# dexv1.net
KiCad netlist of a schematic drawn in EAGLE
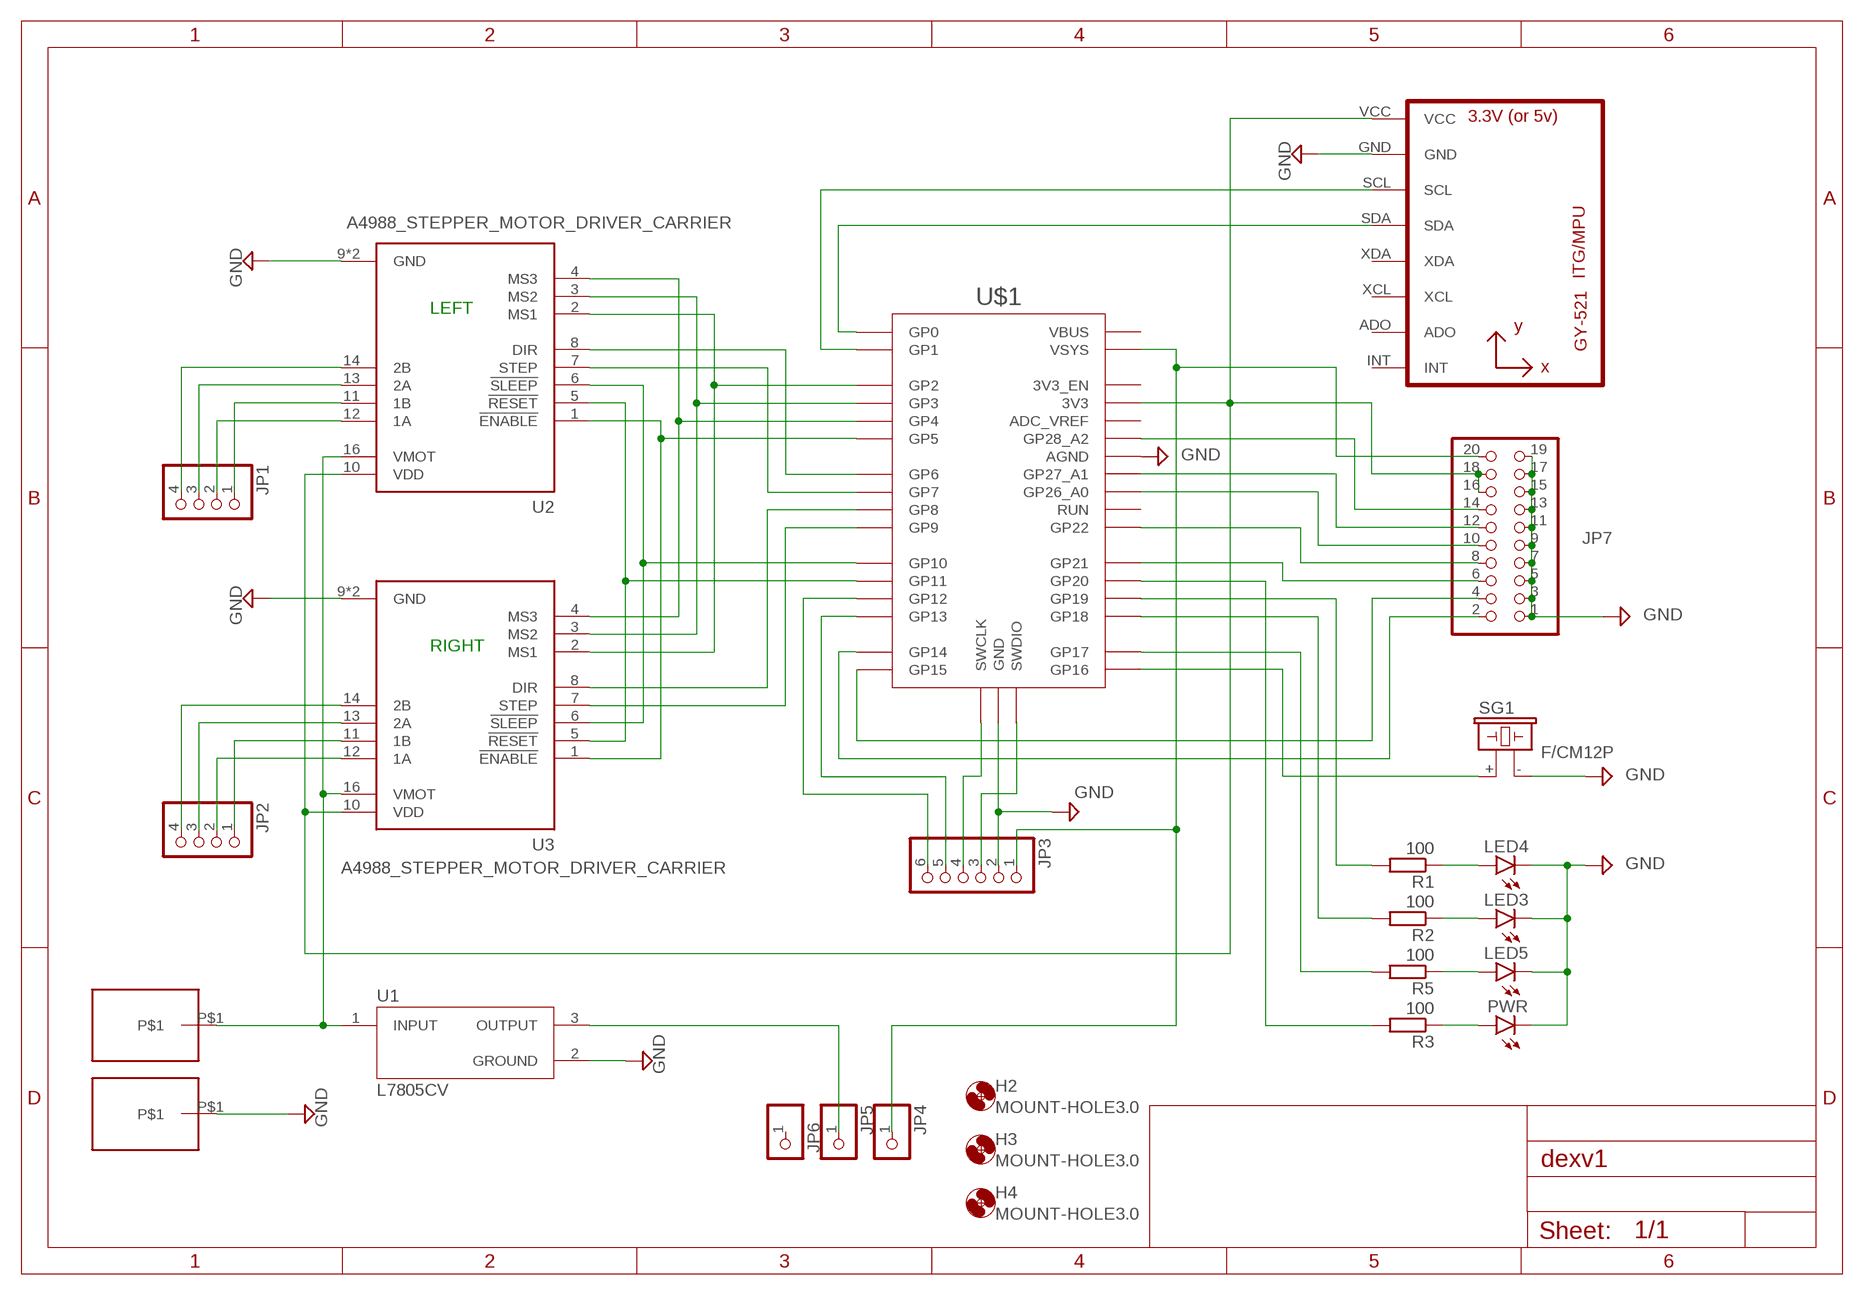
[diagram p0: schematic, sheet 1]

(export (version "E")
  (design (tool "Eeschema 10.0.6"))
  (components
    (comp (ref "H2")
      (value "MOUNT-HOLE3.0")
      (footprint "eagle-import:3,0")
      (libsource (lib "eagle-import") (part "MOUNT-HOLE3.0"))
    )
    (comp (ref "H3")
      (value "MOUNT-HOLE3.0")
      (footprint "eagle-import:3,0")
      (libsource (lib "eagle-import") (part "MOUNT-HOLE3.0"))
    )
    (comp (ref "H4")
      (value "MOUNT-HOLE3.0")
      (footprint "eagle-import:3,0")
      (libsource (lib "eagle-import") (part "MOUNT-HOLE3.0"))
    )
    (comp (ref "JP1")
      (value "PINHD-1X4")
      (footprint "eagle-import:1X04")
      (libsource (lib "eagle-import") (part "PINHD-1X4"))
    )
    (comp (ref "JP2")
      (value "PINHD-1X4")
      (footprint "eagle-import:1X04")
      (libsource (lib "eagle-import") (part "PINHD-1X4"))
    )
    (comp (ref "JP3")
      (value "PINHD-1X6")
      (footprint "eagle-import:1X06")
      (libsource (lib "eagle-import") (part "PINHD-1X6"))
    )
    (comp (ref "JP4")
      (value "PINHD-1X1")
      (footprint "eagle-import:1X01")
      (libsource (lib "eagle-import") (part "PINHD-1X1"))
    )
    (comp (ref "JP5")
      (value "PINHD-1X1")
      (footprint "eagle-import:1X01")
      (libsource (lib "eagle-import") (part "PINHD-1X1"))
    )
    (comp (ref "JP6")
      (value "PINHD-1X1")
      (footprint "eagle-import:1X01")
      (libsource (lib "eagle-import") (part "PINHD-1X1"))
    )
    (comp (ref "JP7")
      (value "PINHD-2X10")
      (footprint "eagle-import:2X10")
      (libsource (lib "eagle-import") (part "PINHD-2X10"))
    )
    (comp (ref "LED3")
      (value "LED5MM")
      (footprint "eagle-import:LED5MM")
      (libsource (lib "eagle-import") (part "LED5MM"))
    )
    (comp (ref "LED4")
      (value "LED5MM")
      (footprint "eagle-import:LED5MM")
      (libsource (lib "eagle-import") (part "LED5MM"))
    )
    (comp (ref "LED5")
      (value "LED5MM")
      (footprint "eagle-import:LED5MM")
      (libsource (lib "eagle-import") (part "LED5MM"))
    )
    (comp (ref "PWR")
      (value "LED5MM")
      (footprint "eagle-import:LED5MM")
      (libsource (lib "eagle-import") (part "LED5MM"))
    )
    (comp (ref "R1")
      (value "100")
      (footprint "eagle-import:0204_7")
      (libsource (lib "eagle-import") (part "R-EU_0204/7"))
    )
    (comp (ref "R2")
      (value "100")
      (footprint "eagle-import:0204_7")
      (libsource (lib "eagle-import") (part "R-EU_0204/7"))
    )
    (comp (ref "R3")
      (value "100")
      (footprint "eagle-import:0204_7")
      (libsource (lib "eagle-import") (part "R-EU_0204/7"))
    )
    (comp (ref "R5")
      (value "100")
      (footprint "eagle-import:0204_7")
      (libsource (lib "eagle-import") (part "R-EU_0204/7"))
    )
    (comp (ref "SG1")
      (value "F/CM12P")
      (footprint "eagle-import:F_CM12P")
      (libsource (lib "eagle-import") (part "F/CM12P"))
    )
    (comp (ref "U$1")
      (value "RPI_PICO-TH")
      (footprint "eagle-import:RPI_PICO_TH")
      (libsource (lib "eagle-import") (part "RPI_PICO-TH"))
    )
    (comp (ref "U$2")
      (value "SMD5X10")
      (footprint "eagle-import:SMD5X10")
      (libsource (lib "eagle-import") (part "SMD5X10"))
    )
    (comp (ref "U$3")
      (value "SMD5X10")
      (footprint "eagle-import:SMD5X10")
      (libsource (lib "eagle-import") (part "SMD5X10"))
    )
    (comp (ref "U1")
      (value "L7805CV")
      (footprint "eagle-import:TO255P1040X460X1968-3")
      (fields (field (name "MF") "STMicroelectronics") (field (name "MP") "L7805C-V"))
      (libsource (lib "eagle-import") (part "L7805CV"))
    )
    (comp (ref "U2")
      (value "A4988_STEPPER_MOTOR_DRIVER_CARRIER")
      (footprint "eagle-import:MODULE_A4988_STEPPER_MOTOR_DRIVER_CARRIER")
      (fields (field (name "MF") "Pololu") (field (name "MP") "A4988 STEPPER MOTOR DRIVER CARRIER"))
      (libsource (lib "eagle-import") (part "A4988_STEPPER_MOTOR_DRIVER_CARRIER"))
    )
    (comp (ref "U3")
      (value "A4988_STEPPER_MOTOR_DRIVER_CARRIER")
      (footprint "eagle-import:MODULE_A4988_STEPPER_MOTOR_DRIVER_CARRIER")
      (fields (field (name "MF") "Pololu") (field (name "MP") "A4988 STEPPER MOTOR DRIVER CARRIER"))
      (libsource (lib "eagle-import") (part "A4988_STEPPER_MOTOR_DRIVER_CARRIER"))
    )
    (comp (ref "U4")
      (value "GY-521MPU6050")
      (footprint "eagle-import:GY-521")
      (fields (field (name "MF") "GODREAM FORDREAM CO., LIMITED") (field (name "MP") "GY-521"))
      (libsource (lib "eagle-import") (part "GY-521MPU6050"))
    )
  )
  (nets
    (net (code "1") (name "GND") (class "Default")
      (node (ref "JP3") (pin "2") (pinfunction "2_2") (pintype "passive"))
      (node (ref "JP7") (pin "1") (pinfunction "1_1") (pintype "passive"))
      (node (ref "JP7") (pin "11") (pinfunction "11_11") (pintype "passive"))
      (node (ref "JP7") (pin "13") (pinfunction "13_13") (pintype "passive"))
      (node (ref "JP7") (pin "15") (pinfunction "15_15") (pintype "passive"))
      (node (ref "JP7") (pin "17") (pinfunction "17_17") (pintype "passive"))
      (node (ref "JP7") (pin "19") (pinfunction "19_19") (pintype "passive"))
      (node (ref "JP7") (pin "3") (pinfunction "3_3") (pintype "passive"))
      (node (ref "JP7") (pin "5") (pinfunction "5_5") (pintype "passive"))
      (node (ref "JP7") (pin "7") (pinfunction "7_7") (pintype "passive"))
      (node (ref "JP7") (pin "9") (pinfunction "9_9") (pintype "passive"))
      (node (ref "LED3") (pin "K") (pinfunction "C_K") (pintype "passive"))
      (node (ref "LED4") (pin "K") (pinfunction "C_K") (pintype "passive"))
      (node (ref "LED5") (pin "K") (pinfunction "C_K") (pintype "passive"))
      (node (ref "PWR") (pin "K") (pinfunction "C_K") (pintype "passive"))
      (node (ref "SG1") (pin "-") (pinfunction "2_-") (pintype "passive"))
      (node (ref "U$1") (pin "AGND") (pinfunction "AGND_AGND") (pintype "bidirectional"))
      (node (ref "U$1") (pin "GND@1") (pinfunction "GND_GND@1") (pintype "bidirectional"))
      (node (ref "U$1") (pin "GND@2") (pinfunction "GND_GND@2") (pintype "bidirectional"))
      (node (ref "U$1") (pin "GND@3") (pinfunction "GND_GND@3") (pintype "bidirectional"))
      (node (ref "U$1") (pin "GND@4") (pinfunction "GND_GND@4") (pintype "bidirectional"))
      (node (ref "U$1") (pin "GND@5") (pinfunction "GND_GND@5") (pintype "bidirectional"))
      (node (ref "U$1") (pin "GND@6") (pinfunction "GND_GND@6") (pintype "bidirectional"))
      (node (ref "U$1") (pin "GND@7") (pinfunction "GND_GND@7") (pintype "bidirectional"))
      (node (ref "U$1") (pin "GND@8") (pinfunction "GND_GND@8") (pintype "bidirectional"))
      (node (ref "U$1") (pin "P$2") (pinfunction "GND_P$2") (pintype "bidirectional"))
      (node (ref "U$3") (pin "P$1") (pinfunction "P$1_P$1") (pintype "bidirectional"))
      (node (ref "U1") (pin "2") (pinfunction "GROUND_2") (pintype "power_in"))
      (node (ref "U2") (pin "15") (pinfunction "GND_15") (pintype "power_in"))
      (node (ref "U2") (pin "9") (pinfunction "GND_9") (pintype "power_in"))
      (node (ref "U3") (pin "15") (pinfunction "GND_15") (pintype "power_in"))
      (node (ref "U3") (pin "9") (pinfunction "GND_9") (pintype "power_in"))
      (node (ref "U4") (pin "GND") (pinfunction "GND_GND") (pintype "bidirectional"))
    )
    (net (code "2") (name "Net-(JP3-Pad1)") (class "Default")
      (node (ref "JP3") (pin "1") (pinfunction "1_1") (pintype "passive"))
      (node (ref "JP4") (pin "1") (pinfunction "1_1") (pintype "passive"))
      (node (ref "JP7") (pin "20") (pinfunction "20_20") (pintype "passive"))
      (node (ref "U$1") (pin "VSYS") (pinfunction "VSYS_VSYS") (pintype "bidirectional"))
    )
    (net (code "3") (name "Net-(JP3-Pad3)") (class "Default")
      (node (ref "JP3") (pin "3") (pinfunction "3_3") (pintype "passive"))
      (node (ref "U$1") (pin "P$3") (pinfunction "SWDIO_P$3") (pintype "bidirectional"))
      (node (ref "U$1") (pin "SWDIO") (pinfunction "SWDIO_SWDIO") (pintype "bidirectional"))
    )
    (net (code "4") (name "Net-(JP3-Pad4)") (class "Default")
      (node (ref "JP3") (pin "4") (pinfunction "4_4") (pintype "passive"))
      (node (ref "U$1") (pin "P$1") (pinfunction "SWCLK_P$1") (pintype "bidirectional"))
      (node (ref "U$1") (pin "SWCLK") (pinfunction "SWCLK_SWCLK") (pintype "bidirectional"))
    )
    (net (code "5") (name "Net-(JP3-Pad5)") (class "Default")
      (node (ref "JP3") (pin "5") (pinfunction "5_5") (pintype "passive"))
      (node (ref "U$1") (pin "GP13") (pinfunction "GP13_GP13") (pintype "bidirectional"))
    )
    (net (code "6") (name "Net-(JP3-Pad6)") (class "Default")
      (node (ref "JP3") (pin "6") (pinfunction "6_6") (pintype "passive"))
      (node (ref "U$1") (pin "GP12") (pinfunction "GP12_GP12") (pintype "bidirectional"))
    )
    (net (code "7") (name "Net-(JP7-Pad2)") (class "Default")
      (node (ref "JP7") (pin "2") (pinfunction "2_2") (pintype "passive"))
      (node (ref "U$1") (pin "GP14") (pinfunction "GP14_GP14") (pintype "bidirectional"))
    )
    (net (code "8") (name "Net-(JP7-Pad4)") (class "Default")
      (node (ref "JP7") (pin "4") (pinfunction "4_4") (pintype "passive"))
      (node (ref "U$1") (pin "GP15") (pinfunction "GP15_GP15") (pintype "bidirectional"))
    )
    (net (code "9") (name "Net-(JP7-Pad6)") (class "Default")
      (node (ref "JP7") (pin "6") (pinfunction "6_6") (pintype "passive"))
      (node (ref "U$1") (pin "GP21") (pinfunction "GP21_GP21") (pintype "bidirectional"))
    )
    (net (code "10") (name "Net-(JP7-Pad8)") (class "Default")
      (node (ref "JP7") (pin "8") (pinfunction "8_8") (pintype "passive"))
      (node (ref "U$1") (pin "GP22") (pinfunction "GP22_GP22") (pintype "bidirectional"))
    )
    (net (code "11") (name "Net-(JP7-Pad10)") (class "Default")
      (node (ref "JP7") (pin "10") (pinfunction "10_10") (pintype "passive"))
      (node (ref "U$1") (pin "GP26_A0") (pinfunction "GP26_A0_GP26_A0") (pintype "bidirectional"))
    )
    (net (code "12") (name "Net-(JP7-Pad12)") (class "Default")
      (node (ref "JP7") (pin "12") (pinfunction "12_12") (pintype "passive"))
      (node (ref "U$1") (pin "GP27_A1") (pinfunction "GP27_A1_GP27_A1") (pintype "bidirectional"))
    )
    (net (code "13") (name "Net-(JP7-Pad14)") (class "Default")
      (node (ref "JP7") (pin "14") (pinfunction "14_14") (pintype "passive"))
      (node (ref "U$1") (pin "GP28_A2") (pinfunction "GP28_A2_GP28_A2") (pintype "bidirectional"))
    )
    (net (code "14") (name "Net-(LED3-PadA)") (class "Default")
      (node (ref "LED3") (pin "A") (pinfunction "A_A") (pintype "passive"))
      (node (ref "R2") (pin "1") (pinfunction "1_1") (pintype "passive"))
    )
    (net (code "15") (name "Net-(LED4-PadA)") (class "Default")
      (node (ref "LED4") (pin "A") (pinfunction "A_A") (pintype "passive"))
      (node (ref "R1") (pin "1") (pinfunction "1_1") (pintype "passive"))
    )
    (net (code "16") (name "Net-(LED5-PadA)") (class "Default")
      (node (ref "LED5") (pin "A") (pinfunction "A_A") (pintype "passive"))
      (node (ref "R5") (pin "1") (pinfunction "1_1") (pintype "passive"))
    )
    (net (code "17") (name "Net-(PWR-PadA)") (class "Default")
      (node (ref "PWR") (pin "A") (pinfunction "A_A") (pintype "passive"))
      (node (ref "R3") (pin "1") (pinfunction "1_1") (pintype "passive"))
    )
    (net (code "18") (name "Net-(R1-Pad2)") (class "Default")
      (node (ref "R1") (pin "2") (pinfunction "2_2") (pintype "passive"))
      (node (ref "U$1") (pin "GP19") (pinfunction "GP19_GP19") (pintype "bidirectional"))
    )
    (net (code "19") (name "Net-(R2-Pad2)") (class "Default")
      (node (ref "R2") (pin "2") (pinfunction "2_2") (pintype "passive"))
      (node (ref "U$1") (pin "GP18") (pinfunction "GP18_GP18") (pintype "bidirectional"))
    )
    (net (code "20") (name "Net-(R3-Pad2)") (class "Default")
      (node (ref "R3") (pin "2") (pinfunction "2_2") (pintype "passive"))
      (node (ref "U$1") (pin "GP20") (pinfunction "GP20_GP20") (pintype "bidirectional"))
    )
    (net (code "21") (name "Net-(R5-Pad2)") (class "Default")
      (node (ref "R5") (pin "2") (pinfunction "2_2") (pintype "passive"))
      (node (ref "U$1") (pin "GP17") (pinfunction "GP17_GP17") (pintype "bidirectional"))
    )
    (net (code "22") (name "Net-(SG1-1)") (class "Default")
      (node (ref "SG1") (pin "+") (pinfunction "1_+") (pintype "passive"))
      (node (ref "U$1") (pin "GP16") (pinfunction "GP16_GP16") (pintype "bidirectional"))
    )
    (net (code "23") (name "Net-(U$1-PadGP0)") (class "Default")
      (node (ref "U$1") (pin "GP0") (pinfunction "GP0_GP0") (pintype "bidirectional"))
      (node (ref "U4") (pin "SDA") (pinfunction "SDA_SDA") (pintype "bidirectional"))
    )
    (net (code "24") (name "Net-(U$1-PadGP1)") (class "Default")
      (node (ref "U$1") (pin "GP1") (pinfunction "GP1_GP1") (pintype "bidirectional"))
      (node (ref "U4") (pin "SCL") (pinfunction "SCL_SCL") (pintype "bidirectional"))
    )
    (net (code "25") (name "Net-(U1-INPUT)") (class "Default")
      (node (ref "U$2") (pin "P$1") (pinfunction "P$1_P$1") (pintype "bidirectional"))
      (node (ref "U1") (pin "1") (pinfunction "INPUT_1") (pintype "input"))
      (node (ref "U2") (pin "16") (pinfunction "VMOT_16") (pintype "power_in"))
      (node (ref "U3") (pin "16") (pinfunction "VMOT_16") (pintype "power_in"))
    )
    (net (code "26") (name "Net-(U1-OUTPUT)") (class "Default")
      (node (ref "JP5") (pin "1") (pinfunction "1_1") (pintype "passive"))
      (node (ref "U1") (pin "3") (pinfunction "OUTPUT_3") (pintype "output"))
    )
    (net (code "27") (name "Net-(U2-1A)") (class "Default")
      (node (ref "JP1") (pin "2") (pinfunction "2_2") (pintype "passive"))
      (node (ref "U2") (pin "12") (pinfunction "1A_12") (pintype "output"))
    )
    (net (code "28") (name "Net-(U2-1B)") (class "Default")
      (node (ref "JP1") (pin "1") (pinfunction "1_1") (pintype "passive"))
      (node (ref "U2") (pin "11") (pinfunction "1B_11") (pintype "output"))
    )
    (net (code "29") (name "Net-(U2-2A)") (class "Default")
      (node (ref "JP1") (pin "3") (pinfunction "3_3") (pintype "passive"))
      (node (ref "U2") (pin "13") (pinfunction "2A_13") (pintype "output"))
    )
    (net (code "30") (name "Net-(U2-2B)") (class "Default")
      (node (ref "JP1") (pin "4") (pinfunction "4_4") (pintype "passive"))
      (node (ref "U2") (pin "14") (pinfunction "2B_14") (pintype "output"))
    )
    (net (code "31") (name "Net-(U2-DIR)") (class "Default")
      (node (ref "U$1") (pin "GP6") (pinfunction "GP6_GP6") (pintype "bidirectional"))
      (node (ref "U2") (pin "8") (pinfunction "DIR_8") (pintype "input"))
    )
    (net (code "32") (name "Net-(U2-MS1)") (class "Default")
      (node (ref "U$1") (pin "GP2") (pinfunction "GP2_GP2") (pintype "bidirectional"))
      (node (ref "U2") (pin "2") (pinfunction "MS1_2") (pintype "input"))
      (node (ref "U3") (pin "2") (pinfunction "MS1_2") (pintype "input"))
    )
    (net (code "33") (name "Net-(U2-MS2)") (class "Default")
      (node (ref "U$1") (pin "GP3") (pinfunction "GP3_GP3") (pintype "bidirectional"))
      (node (ref "U2") (pin "3") (pinfunction "MS2_3") (pintype "input"))
      (node (ref "U3") (pin "3") (pinfunction "MS2_3") (pintype "input"))
    )
    (net (code "34") (name "Net-(U2-MS3)") (class "Default")
      (node (ref "U$1") (pin "GP4") (pinfunction "GP4_GP4") (pintype "bidirectional"))
      (node (ref "U2") (pin "4") (pinfunction "MS3_4") (pintype "input"))
      (node (ref "U3") (pin "4") (pinfunction "MS3_4") (pintype "input"))
    )
    (net (code "35") (name "Net-(U2-STEP)") (class "Default")
      (node (ref "U$1") (pin "GP7") (pinfunction "GP7_GP7") (pintype "bidirectional"))
      (node (ref "U2") (pin "7") (pinfunction "STEP_7") (pintype "input"))
    )
    (net (code "36") (name "Net-(U2-VDD)") (class "Default")
      (node (ref "JP7") (pin "16") (pinfunction "16_16") (pintype "passive"))
      (node (ref "JP7") (pin "18") (pinfunction "18_18") (pintype "passive"))
      (node (ref "U$1") (pin "3V3") (pinfunction "3V3_3V3") (pintype "bidirectional"))
      (node (ref "U2") (pin "10") (pinfunction "VDD_10") (pintype "power_in"))
      (node (ref "U3") (pin "10") (pinfunction "VDD_10") (pintype "power_in"))
      (node (ref "U4") (pin "VCC") (pinfunction "VCC_VCC") (pintype "bidirectional"))
    )
    (net (code "37") (name "Net-(U2-~{ENABLE})") (class "Default")
      (node (ref "U$1") (pin "GP5") (pinfunction "GP5_GP5") (pintype "bidirectional"))
      (node (ref "U2") (pin "1") (pinfunction "~{ENABLE}_1") (pintype "input"))
      (node (ref "U3") (pin "1") (pinfunction "~{ENABLE}_1") (pintype "input"))
    )
    (net (code "38") (name "Net-(U2-~{RESET})") (class "Default")
      (node (ref "U$1") (pin "GP11") (pinfunction "GP11_GP11") (pintype "bidirectional"))
      (node (ref "U2") (pin "5") (pinfunction "~{RESET}_5") (pintype "input"))
      (node (ref "U3") (pin "5") (pinfunction "~{RESET}_5") (pintype "input"))
    )
    (net (code "39") (name "Net-(U2-~{SLEEP})") (class "Default")
      (node (ref "U$1") (pin "GP10") (pinfunction "GP10_GP10") (pintype "bidirectional"))
      (node (ref "U2") (pin "6") (pinfunction "~{SLEEP}_6") (pintype "input"))
      (node (ref "U3") (pin "6") (pinfunction "~{SLEEP}_6") (pintype "input"))
    )
    (net (code "40") (name "Net-(U3-1A)") (class "Default")
      (node (ref "JP2") (pin "2") (pinfunction "2_2") (pintype "passive"))
      (node (ref "U3") (pin "12") (pinfunction "1A_12") (pintype "output"))
    )
    (net (code "41") (name "Net-(U3-1B)") (class "Default")
      (node (ref "JP2") (pin "1") (pinfunction "1_1") (pintype "passive"))
      (node (ref "U3") (pin "11") (pinfunction "1B_11") (pintype "output"))
    )
    (net (code "42") (name "Net-(U3-2A)") (class "Default")
      (node (ref "JP2") (pin "3") (pinfunction "3_3") (pintype "passive"))
      (node (ref "U3") (pin "13") (pinfunction "2A_13") (pintype "output"))
    )
    (net (code "43") (name "Net-(U3-2B)") (class "Default")
      (node (ref "JP2") (pin "4") (pinfunction "4_4") (pintype "passive"))
      (node (ref "U3") (pin "14") (pinfunction "2B_14") (pintype "output"))
    )
    (net (code "44") (name "Net-(U3-DIR)") (class "Default")
      (node (ref "U$1") (pin "GP8") (pinfunction "GP8_GP8") (pintype "bidirectional"))
      (node (ref "U3") (pin "8") (pinfunction "DIR_8") (pintype "input"))
    )
    (net (code "45") (name "Net-(U3-STEP)") (class "Default")
      (node (ref "U$1") (pin "GP9") (pinfunction "GP9_GP9") (pintype "bidirectional"))
      (node (ref "U3") (pin "7") (pinfunction "STEP_7") (pintype "input"))
    )
    (net (code "46") (name "unconnected-(JP6-Pad1)") (class "Default")
      (node (ref "JP6") (pin "1") (pinfunction "1_1") (pintype "passive"))
    )
    (net (code "47") (name "unconnected-(U$1-Pad3V3_EN)") (class "Default")
      (node (ref "U$1") (pin "3V3_EN") (pinfunction "3V3_EN_3V3_EN") (pintype "bidirectional"))
    )
    (net (code "48") (name "unconnected-(U$1-PadADC_VREF)") (class "Default")
      (node (ref "U$1") (pin "ADC_VREF") (pinfunction "ADC_VREF_ADC_VREF") (pintype "bidirectional"))
    )
    (net (code "49") (name "unconnected-(U$1-PadRUN)") (class "Default")
      (node (ref "U$1") (pin "RUN") (pinfunction "RUN_RUN") (pintype "bidirectional"))
    )
    (net (code "50") (name "unconnected-(U$1-PadVBUS)") (class "Default")
      (node (ref "U$1") (pin "VBUS") (pinfunction "VBUS_VBUS") (pintype "bidirectional"))
    )
    (net (code "51") (name "unconnected-(U4-PadADO)") (class "Default")
      (node (ref "U4") (pin "ADO") (pinfunction "ADO_ADO") (pintype "bidirectional"))
    )
    (net (code "52") (name "unconnected-(U4-PadINT)") (class "Default")
      (node (ref "U4") (pin "INT") (pinfunction "INT_INT") (pintype "bidirectional"))
    )
    (net (code "53") (name "unconnected-(U4-PadXCL)") (class "Default")
      (node (ref "U4") (pin "XCL") (pinfunction "XCL_XCL") (pintype "bidirectional"))
    )
    (net (code "54") (name "unconnected-(U4-PadXDA)") (class "Default")
      (node (ref "U4") (pin "XDA") (pinfunction "XDA_XDA") (pintype "bidirectional"))
    )
  )
)
